# stm32l1.net
KiCad netlist of a schematic drawn in EAGLE
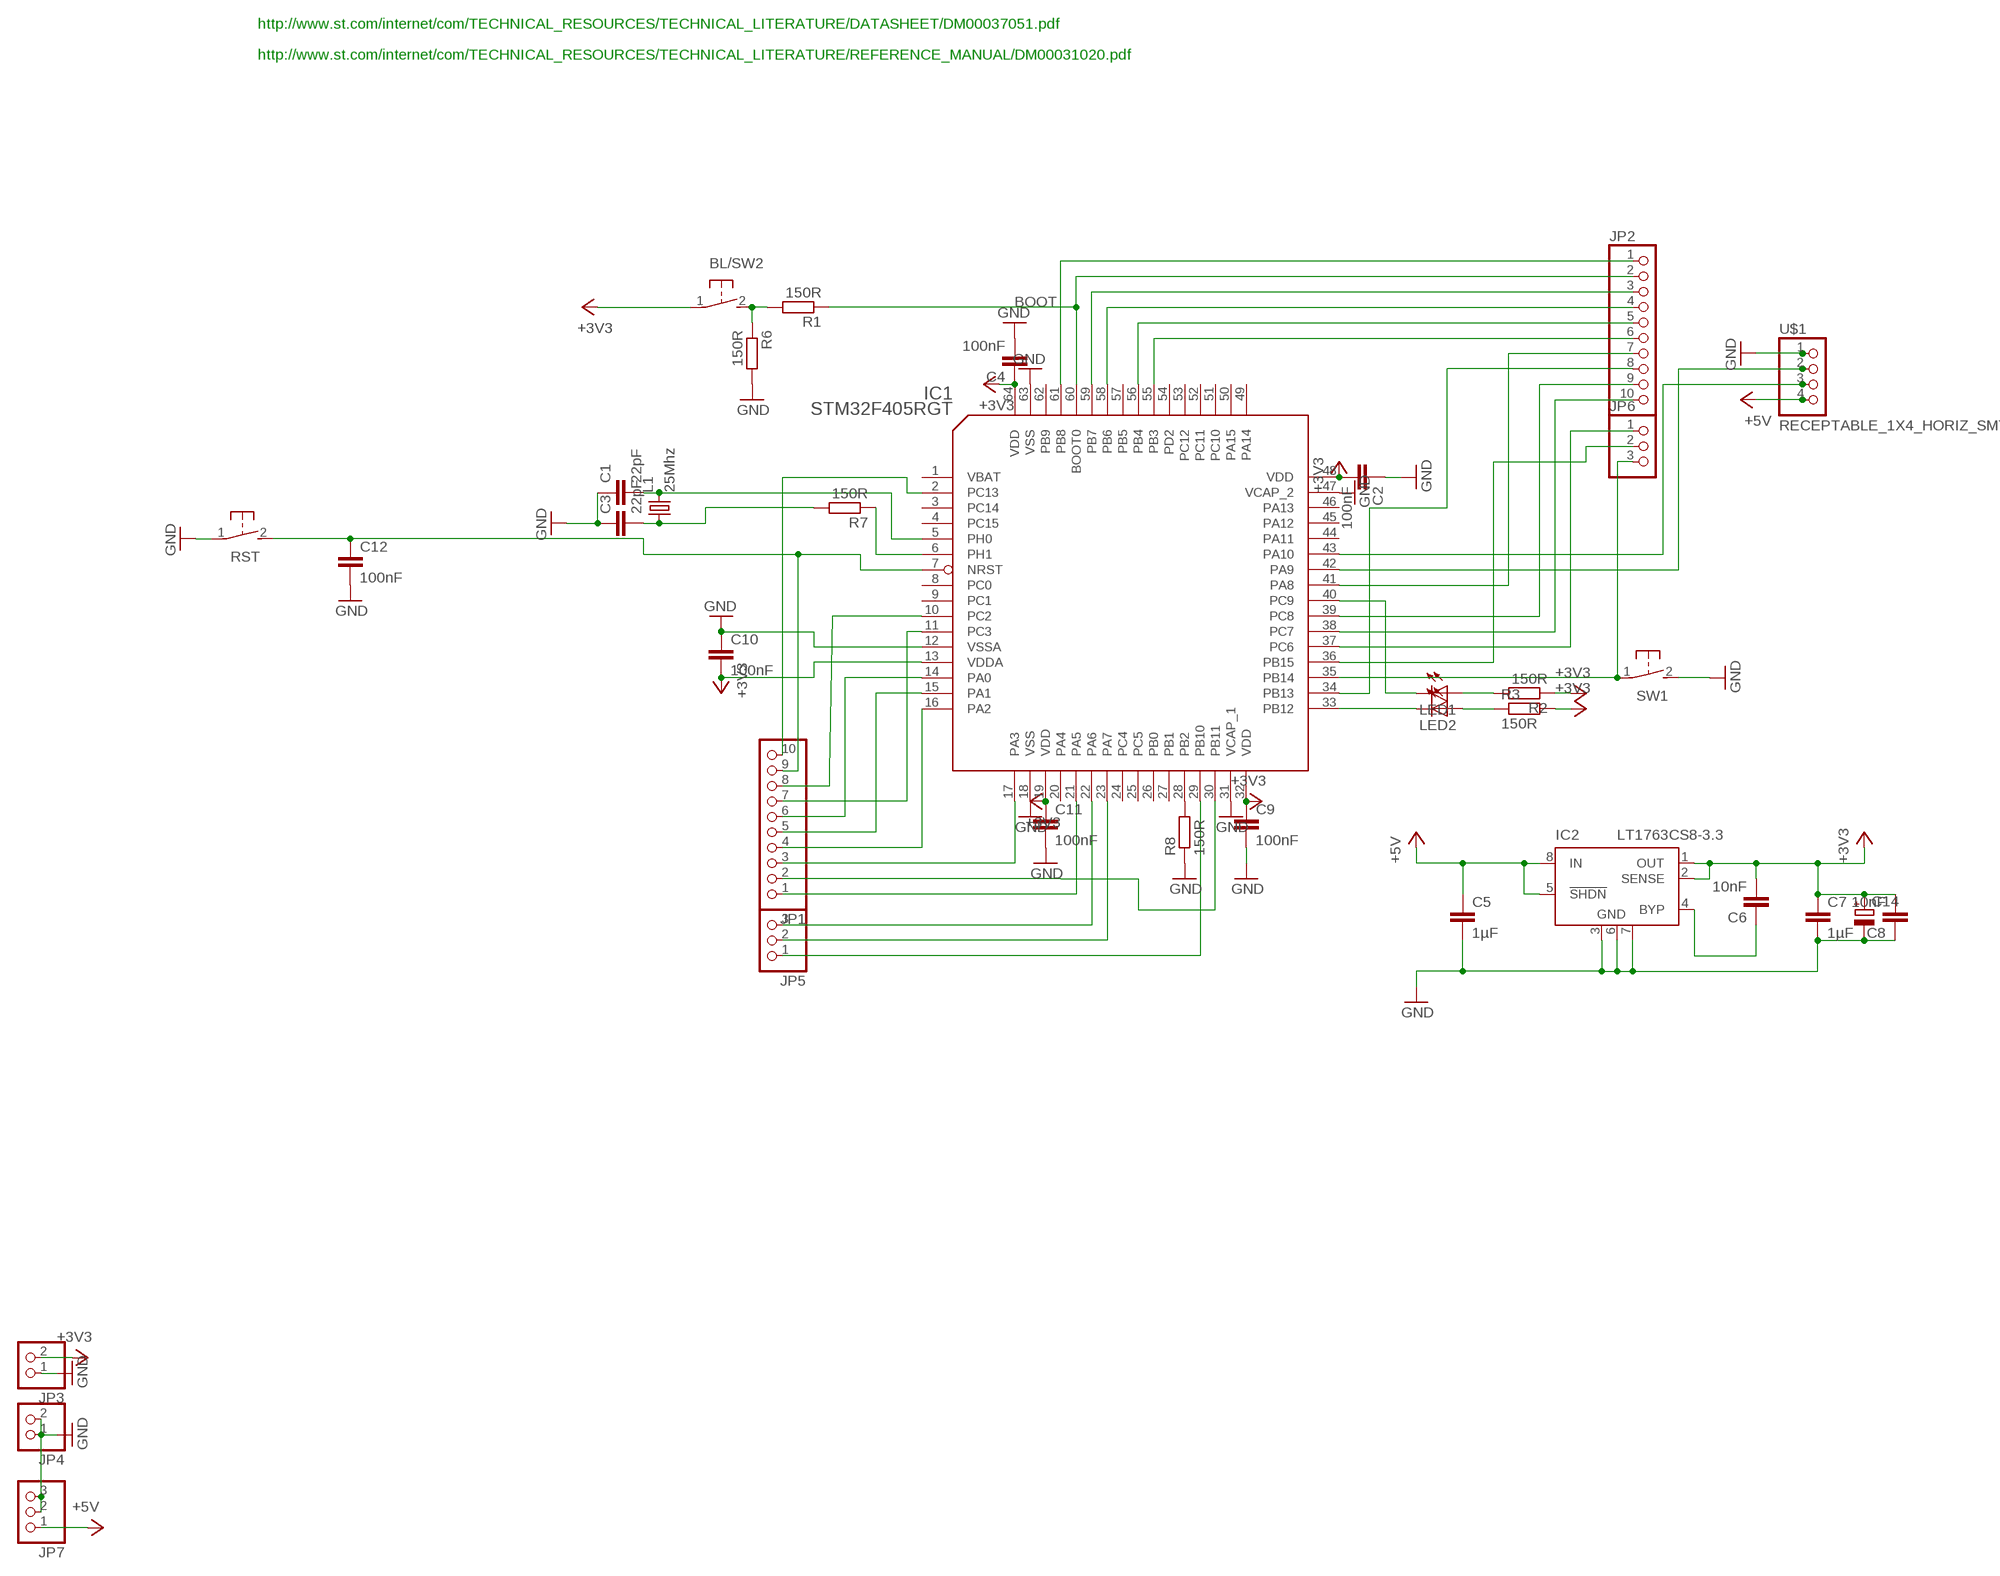
[diagram p0: schematic, sheet 1]

(export (version "E")
  (design (tool "Eeschema 10.0.6"))
  (components
    (comp (ref "BL/SW2")
      (value "SWITCH_MCTAEF")
      (footprint "eagle-import:SWITCH_MCTAEF")
      (libsource (lib "eagle-import") (part "SWITCH_MCTAEF"))
    )
    (comp (ref "C1")
      (value "22pF")
      (footprint "eagle-import:C0402")
      (libsource (lib "eagle-import") (part "C-EUC0402"))
    )
    (comp (ref "C2")
      (value "100nF")
      (footprint "eagle-import:C0402")
      (libsource (lib "eagle-import") (part "C-EUC0402"))
    )
    (comp (ref "C3")
      (value "22pF")
      (footprint "eagle-import:C0402")
      (libsource (lib "eagle-import") (part "C-EUC0402"))
    )
    (comp (ref "C4")
      (value "100nF")
      (footprint "eagle-import:C0402")
      (libsource (lib "eagle-import") (part "C-EUC0402"))
    )
    (comp (ref "C5")
      (value "1µF")
      (footprint "eagle-import:0805")
      (libsource (lib "eagle-import") (part "CAP0805"))
    )
    (comp (ref "C6")
      (value "10nF")
      (footprint "eagle-import:C0402")
      (libsource (lib "eagle-import") (part "C-EUC0402"))
    )
    (comp (ref "C7")
      (value "1µF")
      (footprint "eagle-import:0805")
      (libsource (lib "eagle-import") (part "CAP0805"))
    )
    (comp (ref "C8")
      (value "10nF")
      (footprint "eagle-import:C0402")
      (libsource (lib "eagle-import") (part "C-EUC0402"))
    )
    (comp (ref "C9")
      (value "100nF")
      (footprint "eagle-import:C0402")
      (libsource (lib "eagle-import") (part "C-EUC0402"))
    )
    (comp (ref "C10")
      (value "100nF")
      (footprint "eagle-import:C0402")
      (libsource (lib "eagle-import") (part "C-EUC0402"))
    )
    (comp (ref "C11")
      (value "100nF")
      (footprint "eagle-import:C0402")
      (libsource (lib "eagle-import") (part "C-EUC0402"))
    )
    (comp (ref "C12")
      (value "100nF")
      (footprint "eagle-import:C0402")
      (libsource (lib "eagle-import") (part "C-EUC0402"))
    )
    (comp (ref "C14")
      (value "CPOL-EUSMCA")
      (footprint "eagle-import:SMC_A")
      (libsource (lib "eagle-import") (part "CPOL-EUSMCA"))
    )
    (comp (ref "IC1")
      (value "STM32F405RGT")
      (footprint "eagle-import:LQFP64")
      (libsource (lib "eagle-import") (part "STM32F405RTG"))
    )
    (comp (ref "IC2")
      (value "LT1763CS8-3.3")
      (footprint "eagle-import:SOIC8")
      (libsource (lib "eagle-import") (part "LT1763CS8-3.3"))
    )
    (comp (ref "JP1")
      (value "PINHD-1X10_2.54")
      (footprint "eagle-import:1X10")
      (libsource (lib "eagle-import") (part "PINHD-1X10_2.54"))
    )
    (comp (ref "JP2")
      (value "PINHD-1X10_2.54")
      (footprint "eagle-import:1X10")
      (libsource (lib "eagle-import") (part "PINHD-1X10_2.54"))
    )
    (comp (ref "JP3")
      (value "PINHD-1X02_2.54")
      (footprint "eagle-import:1X02")
      (libsource (lib "eagle-import") (part "PINHD-1X02_2.54"))
    )
    (comp (ref "JP4")
      (value "PINHD-1X02_2.54")
      (footprint "eagle-import:1X02")
      (libsource (lib "eagle-import") (part "PINHD-1X02_2.54"))
    )
    (comp (ref "JP5")
      (value "PINHD-1X03_2.54")
      (footprint "eagle-import:1X03")
      (libsource (lib "eagle-import") (part "PINHD-1X03_2.54"))
    )
    (comp (ref "JP6")
      (value "PINHD-1X03_2.54")
      (footprint "eagle-import:1X03")
      (libsource (lib "eagle-import") (part "PINHD-1X03_2.54"))
    )
    (comp (ref "JP7")
      (value "PINHD-1X03_2.54")
      (footprint "eagle-import:1X03")
      (libsource (lib "eagle-import") (part "PINHD-1X03_2.54"))
    )
    (comp (ref "L1")
      (value "25Mhz")
      (footprint "eagle-import:X22")
      (libsource (lib "eagle-import") (part "X22-OSCILLATOR"))
    )
    (comp (ref "LED1")
      (value "LEDCHIPLED_0805")
      (footprint "eagle-import:CHIPLED_0805")
      (libsource (lib "eagle-import") (part "LEDCHIPLED_0805"))
    )
    (comp (ref "LED2")
      (value "LEDCHIPLED_0805")
      (footprint "eagle-import:CHIPLED_0805")
      (libsource (lib "eagle-import") (part "LEDCHIPLED_0805"))
    )
    (comp (ref "R1")
      (value "150R")
      (footprint "eagle-import:R0402")
      (libsource (lib "eagle-import") (part "R-EU_R0402"))
    )
    (comp (ref "R2")
      (value "150R")
      (footprint "eagle-import:R0402")
      (libsource (lib "eagle-import") (part "R-EU_R0402"))
    )
    (comp (ref "R3")
      (value "150R")
      (footprint "eagle-import:R0402")
      (libsource (lib "eagle-import") (part "R-EU_R0402"))
    )
    (comp (ref "R6")
      (value "150R")
      (footprint "eagle-import:R0402")
      (libsource (lib "eagle-import") (part "R-EU_R0402"))
    )
    (comp (ref "R7")
      (value "150R")
      (footprint "eagle-import:R0402")
      (libsource (lib "eagle-import") (part "R-EU_R0402"))
    )
    (comp (ref "R8")
      (value "150R")
      (footprint "eagle-import:R0402")
      (libsource (lib "eagle-import") (part "R-EU_R0402"))
    )
    (comp (ref "RST")
      (value "SWITCH_MCTAEF")
      (footprint "eagle-import:SWITCH_MCTAEF")
      (libsource (lib "eagle-import") (part "SWITCH_MCTAEF"))
    )
    (comp (ref "SW1")
      (value "SWITCH_MCTAEF")
      (footprint "eagle-import:SWITCH_MCTAEF")
      (libsource (lib "eagle-import") (part "SWITCH_MCTAEF"))
    )
    (comp (ref "U$1")
      (value "RECEPTABLE_1X4_HORIZ_SMT")
      (footprint "eagle-import:RECEPTABLE_1X4_HORIZ_SMT")
      (libsource (lib "eagle-import") (part "RECEPTABLE_1X4_HORIZ_SMT"))
    )
  )
  (nets
    (net (code "1") (name "+3V3") (class "Default")
      (node (ref "BL/SW2") (pin "1") (pinfunction "1_1") (pintype "passive"))
      (node (ref "C10") (pin "2") (pinfunction "2_2") (pintype "passive"))
      (node (ref "C11") (pin "1") (pinfunction "1_1") (pintype "passive"))
      (node (ref "C14") (pin "+") (pinfunction "+_+") (pintype "passive"))
      (node (ref "C2") (pin "2") (pinfunction "2_2") (pintype "passive"))
      (node (ref "C4") (pin "1") (pinfunction "1_1") (pintype "passive"))
      (node (ref "C6") (pin "2") (pinfunction "2_2") (pintype "passive"))
      (node (ref "C7") (pin "1") (pinfunction "1_1") (pintype "passive"))
      (node (ref "C8") (pin "2") (pinfunction "2_2") (pintype "passive"))
      (node (ref "C9") (pin "1") (pinfunction "1_1") (pintype "passive"))
      (node (ref "IC1") (pin "13") (pinfunction "VDDA_13") (pintype "power_in"))
      (node (ref "IC1") (pin "19") (pinfunction "VDD_19") (pintype "power_in"))
      (node (ref "IC1") (pin "32") (pinfunction "VDD_32") (pintype "power_in"))
      (node (ref "IC1") (pin "48") (pinfunction "VDD_48") (pintype "power_in"))
      (node (ref "IC1") (pin "64") (pinfunction "VDD_64") (pintype "power_in"))
      (node (ref "IC2") (pin "1") (pinfunction "OUT_1") (pintype "passive"))
      (node (ref "IC2") (pin "2") (pinfunction "SENSE_2") (pintype "input"))
      (node (ref "JP3") (pin "2") (pinfunction "2_2") (pintype "passive"))
      (node (ref "R2") (pin "1") (pinfunction "1_1") (pintype "passive"))
      (node (ref "R3") (pin "2") (pinfunction "2_2") (pintype "passive"))
    )
    (net (code "2") (name "+5V") (class "Default")
      (node (ref "C5") (pin "1") (pinfunction "1_1") (pintype "passive"))
      (node (ref "IC2") (pin "5") (pinfunction "~{SHDN}_5") (pintype "input"))
      (node (ref "IC2") (pin "8") (pinfunction "IN_8") (pintype "input"))
      (node (ref "JP7") (pin "1") (pinfunction "1_1") (pintype "passive"))
      (node (ref "U$1") (pin "4") (pinfunction "4_4") (pintype "power_in"))
      (node (ref "U$1") (pin "4@1") (pinfunction "4_4@1") (pintype "power_in"))
    )
    (net (code "3") (name "/BOOT") (class "Default")
      (node (ref "IC1") (pin "60") (pinfunction "BOOT0_60") (pintype "bidirectional"))
      (node (ref "JP2") (pin "2") (pinfunction "2_2") (pintype "passive"))
      (node (ref "R1") (pin "1") (pinfunction "1_1") (pintype "passive"))
    )
    (net (code "4") (name "/VBAT") (class "Default")
      (node (ref "IC1") (pin "1") (pinfunction "VBAT_1") (pintype "power_in"))
    )
    (net (code "5") (name "GND") (class "Default")
      (node (ref "C1") (pin "1") (pinfunction "1_1") (pintype "passive"))
      (node (ref "C10") (pin "1") (pinfunction "1_1") (pintype "passive"))
      (node (ref "C11") (pin "2") (pinfunction "2_2") (pintype "passive"))
      (node (ref "C12") (pin "2") (pinfunction "2_2") (pintype "passive"))
      (node (ref "C14") (pin "-") (pinfunction "-_-") (pintype "passive"))
      (node (ref "C2") (pin "1") (pinfunction "1_1") (pintype "passive"))
      (node (ref "C3") (pin "1") (pinfunction "1_1") (pintype "passive"))
      (node (ref "C4") (pin "2") (pinfunction "2_2") (pintype "passive"))
      (node (ref "C5") (pin "2") (pinfunction "2_2") (pintype "passive"))
      (node (ref "C7") (pin "2") (pinfunction "2_2") (pintype "passive"))
      (node (ref "C8") (pin "1") (pinfunction "1_1") (pintype "passive"))
      (node (ref "C9") (pin "2") (pinfunction "2_2") (pintype "passive"))
      (node (ref "IC1") (pin "12") (pinfunction "VSSA_12") (pintype "power_in"))
      (node (ref "IC1") (pin "18") (pinfunction "VSS_18") (pintype "power_in"))
      (node (ref "IC1") (pin "31") (pinfunction "VCAP_1_31") (pintype "passive"))
      (node (ref "IC1") (pin "47") (pinfunction "VCAP_2_47") (pintype "passive"))
      (node (ref "IC1") (pin "63") (pinfunction "VSS_63") (pintype "power_in"))
      (node (ref "IC2") (pin "3") (pinfunction "GND_3") (pintype "power_in"))
      (node (ref "IC2") (pin "6") (pinfunction "GND_6") (pintype "power_in"))
      (node (ref "IC2") (pin "7") (pinfunction "GND_7") (pintype "power_in"))
      (node (ref "JP3") (pin "1") (pinfunction "1_1") (pintype "passive"))
      (node (ref "JP4") (pin "1") (pinfunction "1_1") (pintype "passive"))
      (node (ref "JP4") (pin "2") (pinfunction "2_2") (pintype "passive"))
      (node (ref "JP7") (pin "2") (pinfunction "2_2") (pintype "passive"))
      (node (ref "JP7") (pin "3") (pinfunction "3_3") (pintype "passive"))
      (node (ref "R6") (pin "2") (pinfunction "2_2") (pintype "passive"))
      (node (ref "R8") (pin "1") (pinfunction "1_1") (pintype "passive"))
      (node (ref "RST") (pin "1") (pinfunction "1_1") (pintype "passive"))
      (node (ref "SW1") (pin "2") (pinfunction "2_2") (pintype "passive"))
      (node (ref "U$1") (pin "1") (pinfunction "1_1") (pintype "power_in"))
      (node (ref "U$1") (pin "1@1") (pinfunction "1_1@1") (pintype "power_in"))
    )
    (net (code "6") (name "Net-(BL/SW2-Pad2)") (class "Default")
      (node (ref "BL/SW2") (pin "2") (pinfunction "2_2") (pintype "passive"))
      (node (ref "R1") (pin "2") (pinfunction "2_2") (pintype "passive"))
      (node (ref "R6") (pin "1") (pinfunction "1_1") (pintype "passive"))
    )
    (net (code "7") (name "Net-(C3-Pad2)") (class "Default")
      (node (ref "C3") (pin "2") (pinfunction "2_2") (pintype "passive"))
      (node (ref "L1") (pin "1") (pinfunction "1_1") (pintype "passive"))
      (node (ref "R7") (pin "2") (pinfunction "2_2") (pintype "passive"))
    )
    (net (code "8") (name "Net-(IC1-NRST)") (class "Default")
      (node (ref "C12") (pin "1") (pinfunction "1_1") (pintype "passive"))
      (node (ref "IC1") (pin "7") (pinfunction "NRST_7") (pintype "input"))
      (node (ref "JP1") (pin "9") (pinfunction "9_9") (pintype "passive"))
      (node (ref "RST") (pin "2") (pinfunction "2_2") (pintype "passive"))
    )
    (net (code "9") (name "Net-(IC1-PA0)") (class "Default")
      (node (ref "IC1") (pin "14") (pinfunction "PA0_14") (pintype "bidirectional"))
      (node (ref "JP1") (pin "6") (pinfunction "6_6") (pintype "passive"))
    )
    (net (code "10") (name "Net-(IC1-PA1)") (class "Default")
      (node (ref "IC1") (pin "15") (pinfunction "PA1_15") (pintype "bidirectional"))
      (node (ref "JP1") (pin "5") (pinfunction "5_5") (pintype "passive"))
    )
    (net (code "11") (name "Net-(IC1-PA2)") (class "Default")
      (node (ref "IC1") (pin "16") (pinfunction "PA2_16") (pintype "bidirectional"))
      (node (ref "JP1") (pin "4") (pinfunction "4_4") (pintype "passive"))
    )
    (net (code "12") (name "Net-(IC1-PA3)") (class "Default")
      (node (ref "IC1") (pin "17") (pinfunction "PA3_17") (pintype "bidirectional"))
      (node (ref "JP1") (pin "3") (pinfunction "3_3") (pintype "passive"))
    )
    (net (code "13") (name "Net-(IC1-PA5)") (class "Default")
      (node (ref "IC1") (pin "21") (pinfunction "PA5_21") (pintype "bidirectional"))
      (node (ref "JP1") (pin "1") (pinfunction "1_1") (pintype "passive"))
    )
    (net (code "14") (name "Net-(IC1-PA6)") (class "Default")
      (node (ref "IC1") (pin "22") (pinfunction "PA6_22") (pintype "bidirectional"))
      (node (ref "JP5") (pin "3") (pinfunction "3_3") (pintype "passive"))
    )
    (net (code "15") (name "Net-(IC1-PA7)") (class "Default")
      (node (ref "IC1") (pin "23") (pinfunction "PA7_23") (pintype "bidirectional"))
      (node (ref "JP5") (pin "2") (pinfunction "2_2") (pintype "passive"))
    )
    (net (code "16") (name "Net-(IC1-PA8)") (class "Default")
      (node (ref "IC1") (pin "41") (pinfunction "PA8_41") (pintype "bidirectional"))
      (node (ref "JP2") (pin "7") (pinfunction "7_7") (pintype "passive"))
    )
    (net (code "17") (name "Net-(IC1-PA9)") (class "Default")
      (node (ref "IC1") (pin "42") (pinfunction "PA9_42") (pintype "bidirectional"))
      (node (ref "U$1") (pin "2") (pinfunction "2_2") (pintype "power_in"))
      (node (ref "U$1") (pin "2@1") (pinfunction "2_2@1") (pintype "power_in"))
    )
    (net (code "18") (name "Net-(IC1-PA10)") (class "Default")
      (node (ref "IC1") (pin "43") (pinfunction "PA10_43") (pintype "bidirectional"))
      (node (ref "U$1") (pin "3") (pinfunction "3_3") (pintype "power_in"))
      (node (ref "U$1") (pin "3@1") (pinfunction "3_3@1") (pintype "power_in"))
    )
    (net (code "19") (name "Net-(IC1-PB2)") (class "Default")
      (node (ref "IC1") (pin "28") (pinfunction "PB2_28") (pintype "bidirectional"))
      (node (ref "R8") (pin "2") (pinfunction "2_2") (pintype "passive"))
    )
    (net (code "20") (name "Net-(IC1-PB3)") (class "Default")
      (node (ref "IC1") (pin "55") (pinfunction "PB3_55") (pintype "bidirectional"))
      (node (ref "JP2") (pin "6") (pinfunction "6_6") (pintype "passive"))
    )
    (net (code "21") (name "Net-(IC1-PB4)") (class "Default")
      (node (ref "IC1") (pin "56") (pinfunction "PB4_56") (pintype "bidirectional"))
      (node (ref "JP2") (pin "5") (pinfunction "5_5") (pintype "passive"))
    )
    (net (code "22") (name "Net-(IC1-PB6)") (class "Default")
      (node (ref "IC1") (pin "58") (pinfunction "PB6_58") (pintype "bidirectional"))
      (node (ref "JP2") (pin "4") (pinfunction "4_4") (pintype "passive"))
    )
    (net (code "23") (name "Net-(IC1-PB7)") (class "Default")
      (node (ref "IC1") (pin "59") (pinfunction "PB7_59") (pintype "bidirectional"))
      (node (ref "JP2") (pin "3") (pinfunction "3_3") (pintype "passive"))
    )
    (net (code "24") (name "Net-(IC1-PB8)") (class "Default")
      (node (ref "IC1") (pin "61") (pinfunction "PB8_61") (pintype "bidirectional"))
      (node (ref "JP2") (pin "1") (pinfunction "1_1") (pintype "passive"))
    )
    (net (code "25") (name "Net-(IC1-PB10)") (class "Default")
      (node (ref "IC1") (pin "29") (pinfunction "PB10_29") (pintype "bidirectional"))
      (node (ref "JP5") (pin "1") (pinfunction "1_1") (pintype "passive"))
    )
    (net (code "26") (name "Net-(IC1-PB11)") (class "Default")
      (node (ref "IC1") (pin "30") (pinfunction "PB11_30") (pintype "bidirectional"))
      (node (ref "JP1") (pin "2") (pinfunction "2_2") (pintype "passive"))
    )
    (net (code "27") (name "Net-(IC1-PB12)") (class "Default")
      (node (ref "IC1") (pin "33") (pinfunction "PB12_33") (pintype "bidirectional"))
      (node (ref "LED2") (pin "C") (pinfunction "C_C") (pintype "passive"))
    )
    (net (code "28") (name "Net-(IC1-PB13)") (class "Default")
      (node (ref "IC1") (pin "34") (pinfunction "PB13_34") (pintype "bidirectional"))
      (node (ref "JP2") (pin "8") (pinfunction "8_8") (pintype "passive"))
    )
    (net (code "29") (name "Net-(IC1-PB14)") (class "Default")
      (node (ref "IC1") (pin "35") (pinfunction "PB14_35") (pintype "bidirectional"))
      (node (ref "JP6") (pin "3") (pinfunction "3_3") (pintype "passive"))
      (node (ref "SW1") (pin "1") (pinfunction "1_1") (pintype "passive"))
    )
    (net (code "30") (name "Net-(IC1-PB15)") (class "Default")
      (node (ref "IC1") (pin "36") (pinfunction "PB15_36") (pintype "bidirectional"))
      (node (ref "JP6") (pin "2") (pinfunction "2_2") (pintype "passive"))
    )
    (net (code "31") (name "Net-(IC1-PC2)") (class "Default")
      (node (ref "IC1") (pin "10") (pinfunction "PC2_10") (pintype "bidirectional"))
      (node (ref "JP1") (pin "8") (pinfunction "8_8") (pintype "passive"))
    )
    (net (code "32") (name "Net-(IC1-PC3)") (class "Default")
      (node (ref "IC1") (pin "11") (pinfunction "PC3_11") (pintype "bidirectional"))
      (node (ref "JP1") (pin "7") (pinfunction "7_7") (pintype "passive"))
    )
    (net (code "33") (name "Net-(IC1-PC6)") (class "Default")
      (node (ref "IC1") (pin "37") (pinfunction "PC6_37") (pintype "bidirectional"))
      (node (ref "JP6") (pin "1") (pinfunction "1_1") (pintype "passive"))
    )
    (net (code "34") (name "Net-(IC1-PC7)") (class "Default")
      (node (ref "IC1") (pin "38") (pinfunction "PC7_38") (pintype "bidirectional"))
      (node (ref "JP2") (pin "10") (pinfunction "10_10") (pintype "passive"))
    )
    (net (code "35") (name "Net-(IC1-PC8)") (class "Default")
      (node (ref "IC1") (pin "39") (pinfunction "PC8_39") (pintype "bidirectional"))
      (node (ref "JP2") (pin "9") (pinfunction "9_9") (pintype "passive"))
    )
    (net (code "36") (name "Net-(IC1-PC9)") (class "Default")
      (node (ref "IC1") (pin "40") (pinfunction "PC9_40") (pintype "bidirectional"))
      (node (ref "LED1") (pin "C") (pinfunction "C_C") (pintype "passive"))
    )
    (net (code "37") (name "Net-(IC1-PC13)") (class "Default")
      (node (ref "IC1") (pin "2") (pinfunction "PC13_2") (pintype "bidirectional"))
      (node (ref "JP1") (pin "10") (pinfunction "10_10") (pintype "passive"))
    )
    (net (code "38") (name "Net-(IC1-PH0)") (class "Default")
      (node (ref "C1") (pin "2") (pinfunction "2_2") (pintype "passive"))
      (node (ref "IC1") (pin "5") (pinfunction "PH0_5") (pintype "bidirectional"))
      (node (ref "L1") (pin "3") (pinfunction "2_3") (pintype "passive"))
    )
    (net (code "39") (name "Net-(IC1-PH1)") (class "Default")
      (node (ref "IC1") (pin "6") (pinfunction "PH1_6") (pintype "bidirectional"))
      (node (ref "R7") (pin "1") (pinfunction "1_1") (pintype "passive"))
    )
    (net (code "40") (name "Net-(IC2-BYP)") (class "Default")
      (node (ref "C6") (pin "1") (pinfunction "1_1") (pintype "passive"))
      (node (ref "IC2") (pin "4") (pinfunction "BYP_4") (pintype "input"))
    )
    (net (code "41") (name "Net-(LED1-PadA)") (class "Default")
      (node (ref "LED1") (pin "A") (pinfunction "A_A") (pintype "passive"))
      (node (ref "R2") (pin "2") (pinfunction "2_2") (pintype "passive"))
    )
    (net (code "42") (name "Net-(LED2-PadA)") (class "Default")
      (node (ref "LED2") (pin "A") (pinfunction "A_A") (pintype "passive"))
      (node (ref "R3") (pin "1") (pinfunction "1_1") (pintype "passive"))
    )
    (net (code "43") (name "unconnected-(IC1-PA4-Pad20)") (class "Default")
      (node (ref "IC1") (pin "20") (pinfunction "PA4_20") (pintype "bidirectional"))
    )
    (net (code "44") (name "unconnected-(IC1-PA11-Pad44)") (class "Default")
      (node (ref "IC1") (pin "44") (pinfunction "PA11_44") (pintype "bidirectional"))
    )
    (net (code "45") (name "unconnected-(IC1-PA12-Pad45)") (class "Default")
      (node (ref "IC1") (pin "45") (pinfunction "PA12_45") (pintype "bidirectional"))
    )
    (net (code "46") (name "unconnected-(IC1-PA13-Pad46)") (class "Default")
      (node (ref "IC1") (pin "46") (pinfunction "PA13_46") (pintype "bidirectional"))
    )
    (net (code "47") (name "unconnected-(IC1-PA14-Pad49)") (class "Default")
      (node (ref "IC1") (pin "49") (pinfunction "PA14_49") (pintype "bidirectional"))
    )
    (net (code "48") (name "unconnected-(IC1-PA15-Pad50)") (class "Default")
      (node (ref "IC1") (pin "50") (pinfunction "PA15_50") (pintype "bidirectional"))
    )
    (net (code "49") (name "unconnected-(IC1-PB0-Pad26)") (class "Default")
      (node (ref "IC1") (pin "26") (pinfunction "PB0_26") (pintype "bidirectional"))
    )
    (net (code "50") (name "unconnected-(IC1-PB1-Pad27)") (class "Default")
      (node (ref "IC1") (pin "27") (pinfunction "PB1_27") (pintype "bidirectional"))
    )
    (net (code "51") (name "unconnected-(IC1-PB5-Pad57)") (class "Default")
      (node (ref "IC1") (pin "57") (pinfunction "PB5_57") (pintype "bidirectional"))
    )
    (net (code "52") (name "unconnected-(IC1-PB9-Pad62)") (class "Default")
      (node (ref "IC1") (pin "62") (pinfunction "PB9_62") (pintype "bidirectional"))
    )
    (net (code "53") (name "unconnected-(IC1-PC0-Pad8)") (class "Default")
      (node (ref "IC1") (pin "8") (pinfunction "PC0_8") (pintype "bidirectional"))
    )
    (net (code "54") (name "unconnected-(IC1-PC1-Pad9)") (class "Default")
      (node (ref "IC1") (pin "9") (pinfunction "PC1_9") (pintype "bidirectional"))
    )
    (net (code "55") (name "unconnected-(IC1-PC4-Pad24)") (class "Default")
      (node (ref "IC1") (pin "24") (pinfunction "PC4_24") (pintype "bidirectional"))
    )
    (net (code "56") (name "unconnected-(IC1-PC5-Pad25)") (class "Default")
      (node (ref "IC1") (pin "25") (pinfunction "PC5_25") (pintype "bidirectional"))
    )
    (net (code "57") (name "unconnected-(IC1-PC10-Pad51)") (class "Default")
      (node (ref "IC1") (pin "51") (pinfunction "PC10_51") (pintype "bidirectional"))
    )
    (net (code "58") (name "unconnected-(IC1-PC11-Pad52)") (class "Default")
      (node (ref "IC1") (pin "52") (pinfunction "PC11_52") (pintype "bidirectional"))
    )
    (net (code "59") (name "unconnected-(IC1-PC12-Pad53)") (class "Default")
      (node (ref "IC1") (pin "53") (pinfunction "PC12_53") (pintype "bidirectional"))
    )
    (net (code "60") (name "unconnected-(IC1-PC14-Pad3)") (class "Default")
      (node (ref "IC1") (pin "3") (pinfunction "PC14_3") (pintype "bidirectional"))
    )
    (net (code "61") (name "unconnected-(IC1-PC15-Pad4)") (class "Default")
      (node (ref "IC1") (pin "4") (pinfunction "PC15_4") (pintype "bidirectional"))
    )
    (net (code "62") (name "unconnected-(IC1-PD2-Pad54)") (class "Default")
      (node (ref "IC1") (pin "54") (pinfunction "PD2_54") (pintype "bidirectional"))
    )
  )
)
